# DAC.net
KiCad netlist of a schematic drawn in Altium Designer
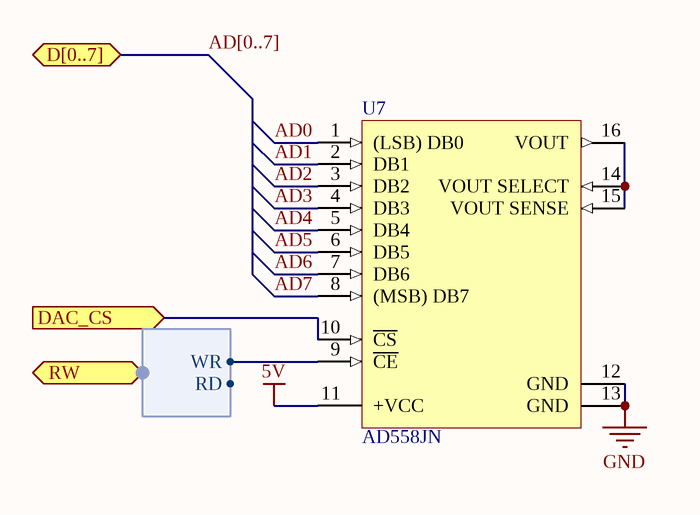
[diagram p0: DAC.SchDoc]

(export (version "E")
  (design (tool "Eeschema 10.0.6"))
  (components
    (comp (ref "U7")
      (value "AD558JN")
      (footprint "N-16")
      (description "Single 8-Bit Low Cost Complete uP-Compatible DACPORT, 0 to +70 degC, N-16, Tube")
      (fields (field (name "GENERIC PART NUMBER") "AD558") (field (name "MANUFACTURER") "Analog Devices"))
      (libsource (lib "Altium Content Vault") (part "ADI-AD558-N-16"))
    )
  )
  (nets
    (net (code "2") (name "/AD0") (class "Default")
      (node (ref "U7") (pin "1") (pinfunction "(LSB)_DB0_1") (pintype "input"))
    )
    (net (code "3") (name "/AD1") (class "Default")
      (node (ref "U7") (pin "2") (pinfunction "DB1_2") (pintype "input"))
    )
    (net (code "4") (name "/AD2") (class "Default")
      (node (ref "U7") (pin "3") (pinfunction "DB2_3") (pintype "input"))
    )
    (net (code "5") (name "/AD3") (class "Default")
      (node (ref "U7") (pin "4") (pinfunction "DB3_4") (pintype "input"))
    )
    (net (code "6") (name "/AD4") (class "Default")
      (node (ref "U7") (pin "5") (pinfunction "DB4_5") (pintype "input"))
    )
    (net (code "7") (name "/AD5") (class "Default")
      (node (ref "U7") (pin "6") (pinfunction "DB5_6") (pintype "input"))
    )
    (net (code "8") (name "/AD6") (class "Default")
      (node (ref "U7") (pin "7") (pinfunction "DB6_7") (pintype "input"))
    )
    (net (code "9") (name "/AD7") (class "Default")
      (node (ref "U7") (pin "8") (pinfunction "(MSB)_DB7_8") (pintype "input"))
    )
    (net (code "11") (name "/DAC_CS") (class "Default")
      (node (ref "U7") (pin "10") (pinfunction "~{CS}_10") (pintype "input"))
    )
    (net (code "12") (name "/WR") (class "Default")
      (node (ref "U7") (pin "9") (pinfunction "~{CE}_9") (pintype "input"))
    )
    (net (code "14") (name "5V") (class "Default")
      (node (ref "U7") (pin "11") (pinfunction "+VCC_11") (pintype "power_in"))
    )
    (net (code "15") (name "GND") (class "Default")
      (node (ref "U7") (pin "12") (pinfunction "GND_12") (pintype "power_in"))
      (node (ref "U7") (pin "13") (pinfunction "GND_13") (pintype "power_in"))
    )
    (net (code "16") (name "Net-(U7-VOUT)") (class "Default")
      (node (ref "U7") (pin "14") (pinfunction "VOUT_SELECT_14") (pintype "input"))
      (node (ref "U7") (pin "15") (pinfunction "VOUT_SENSE_15") (pintype "input"))
      (node (ref "U7") (pin "16") (pinfunction "VOUT_16") (pintype "output"))
    )
  )
)
